# humanoid-17.net
KiCad netlist of a schematic drawn in EAGLE
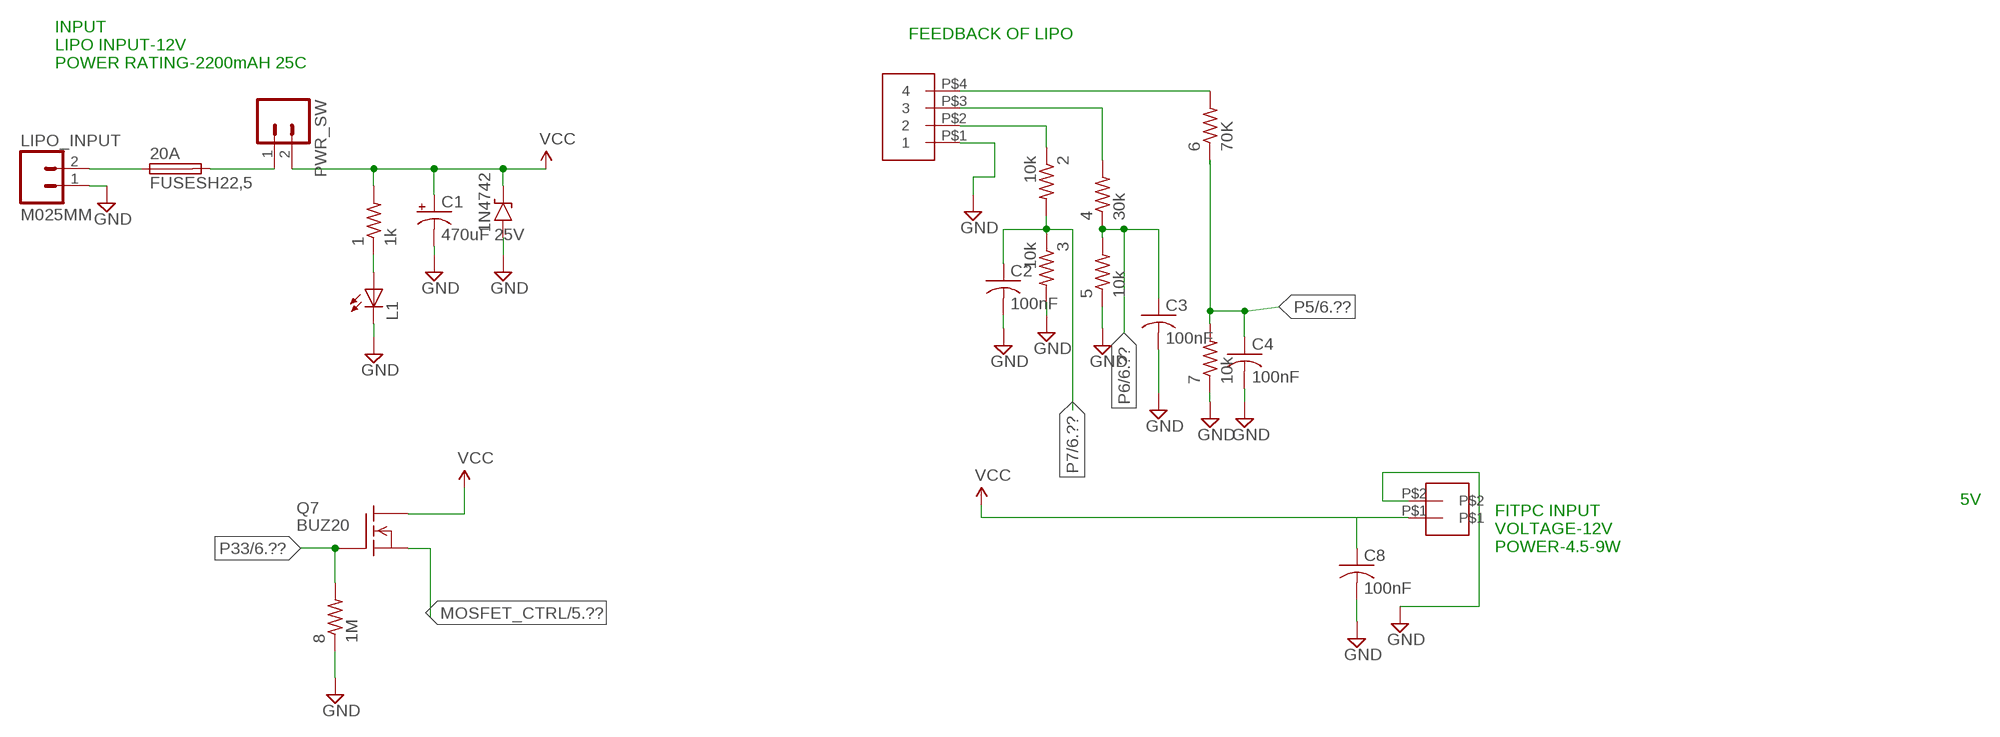
[diagram p0: schematic, sheet 1]
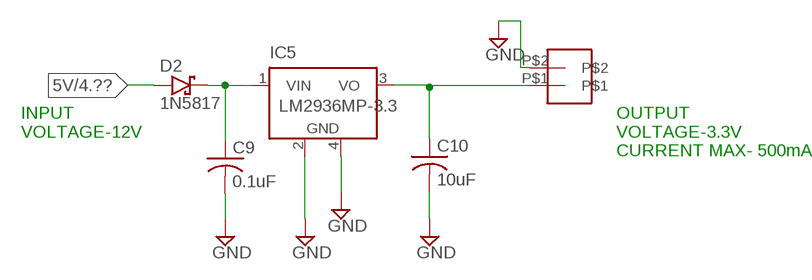
[diagram p1: schematic, sheet 2]
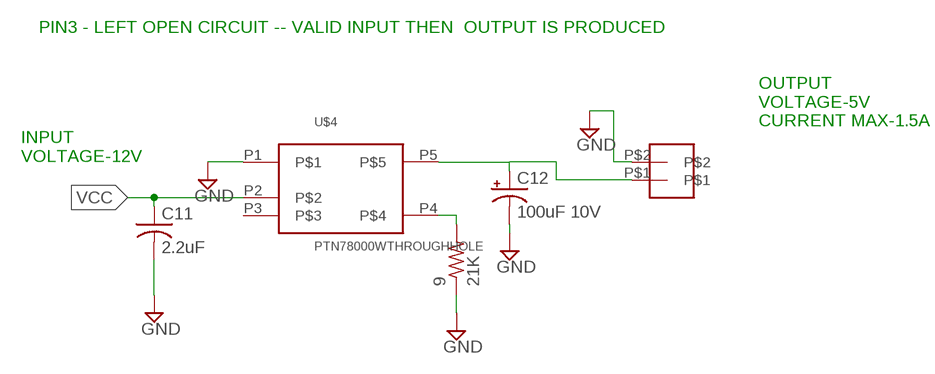
[diagram p2: schematic, sheet 3]
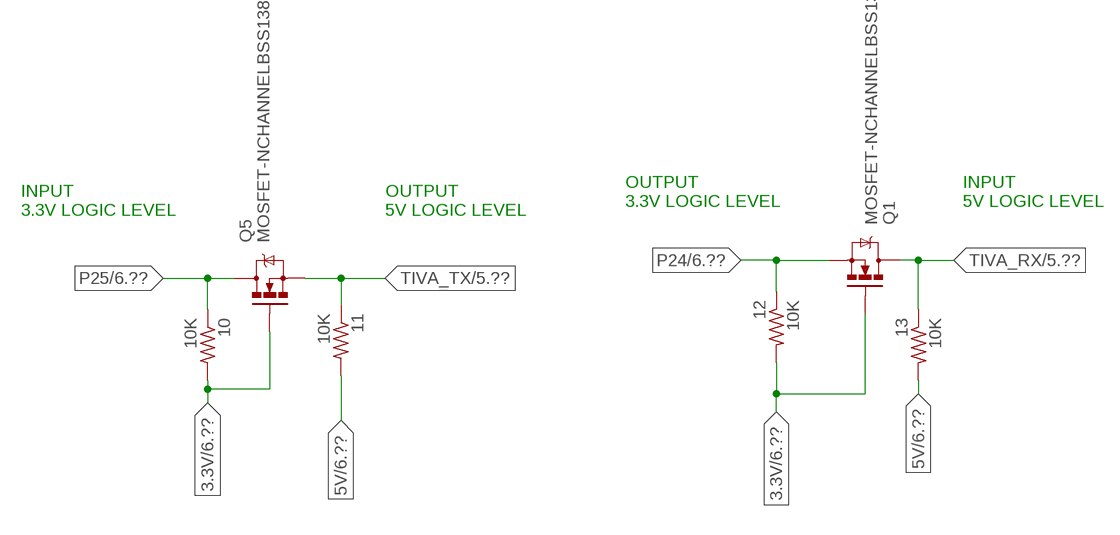
[diagram p3: schematic, sheet 4]
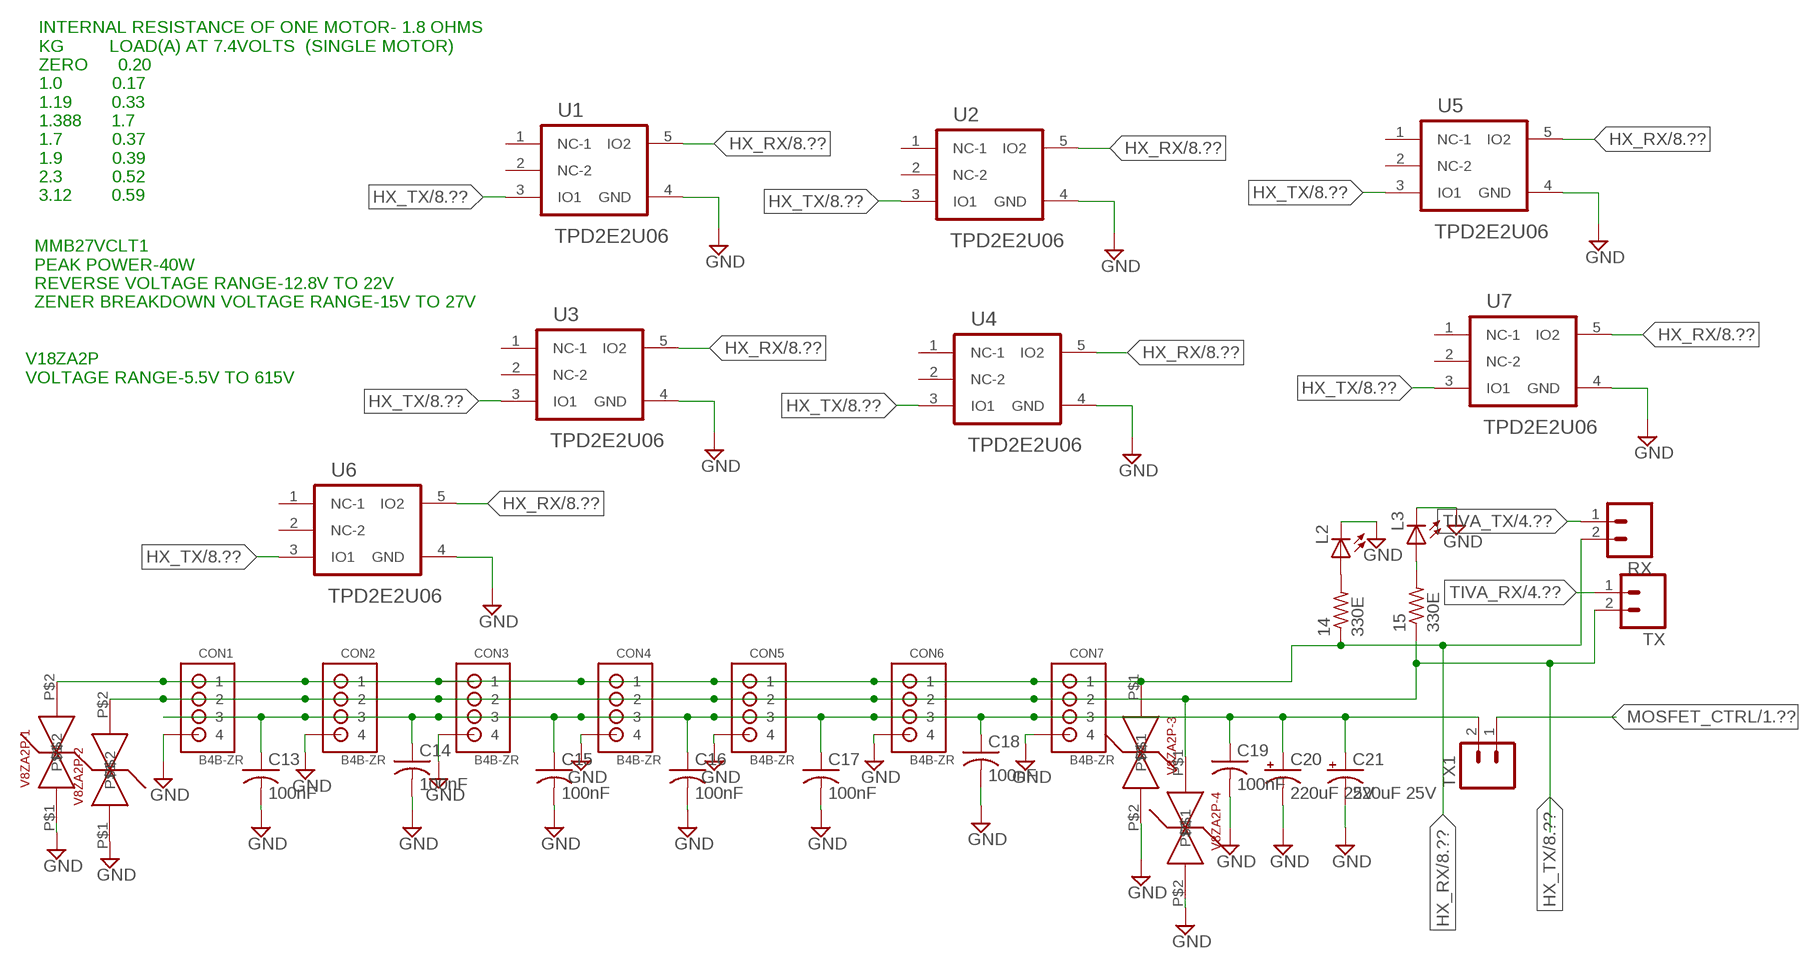
[diagram p4: schematic, sheet 5]
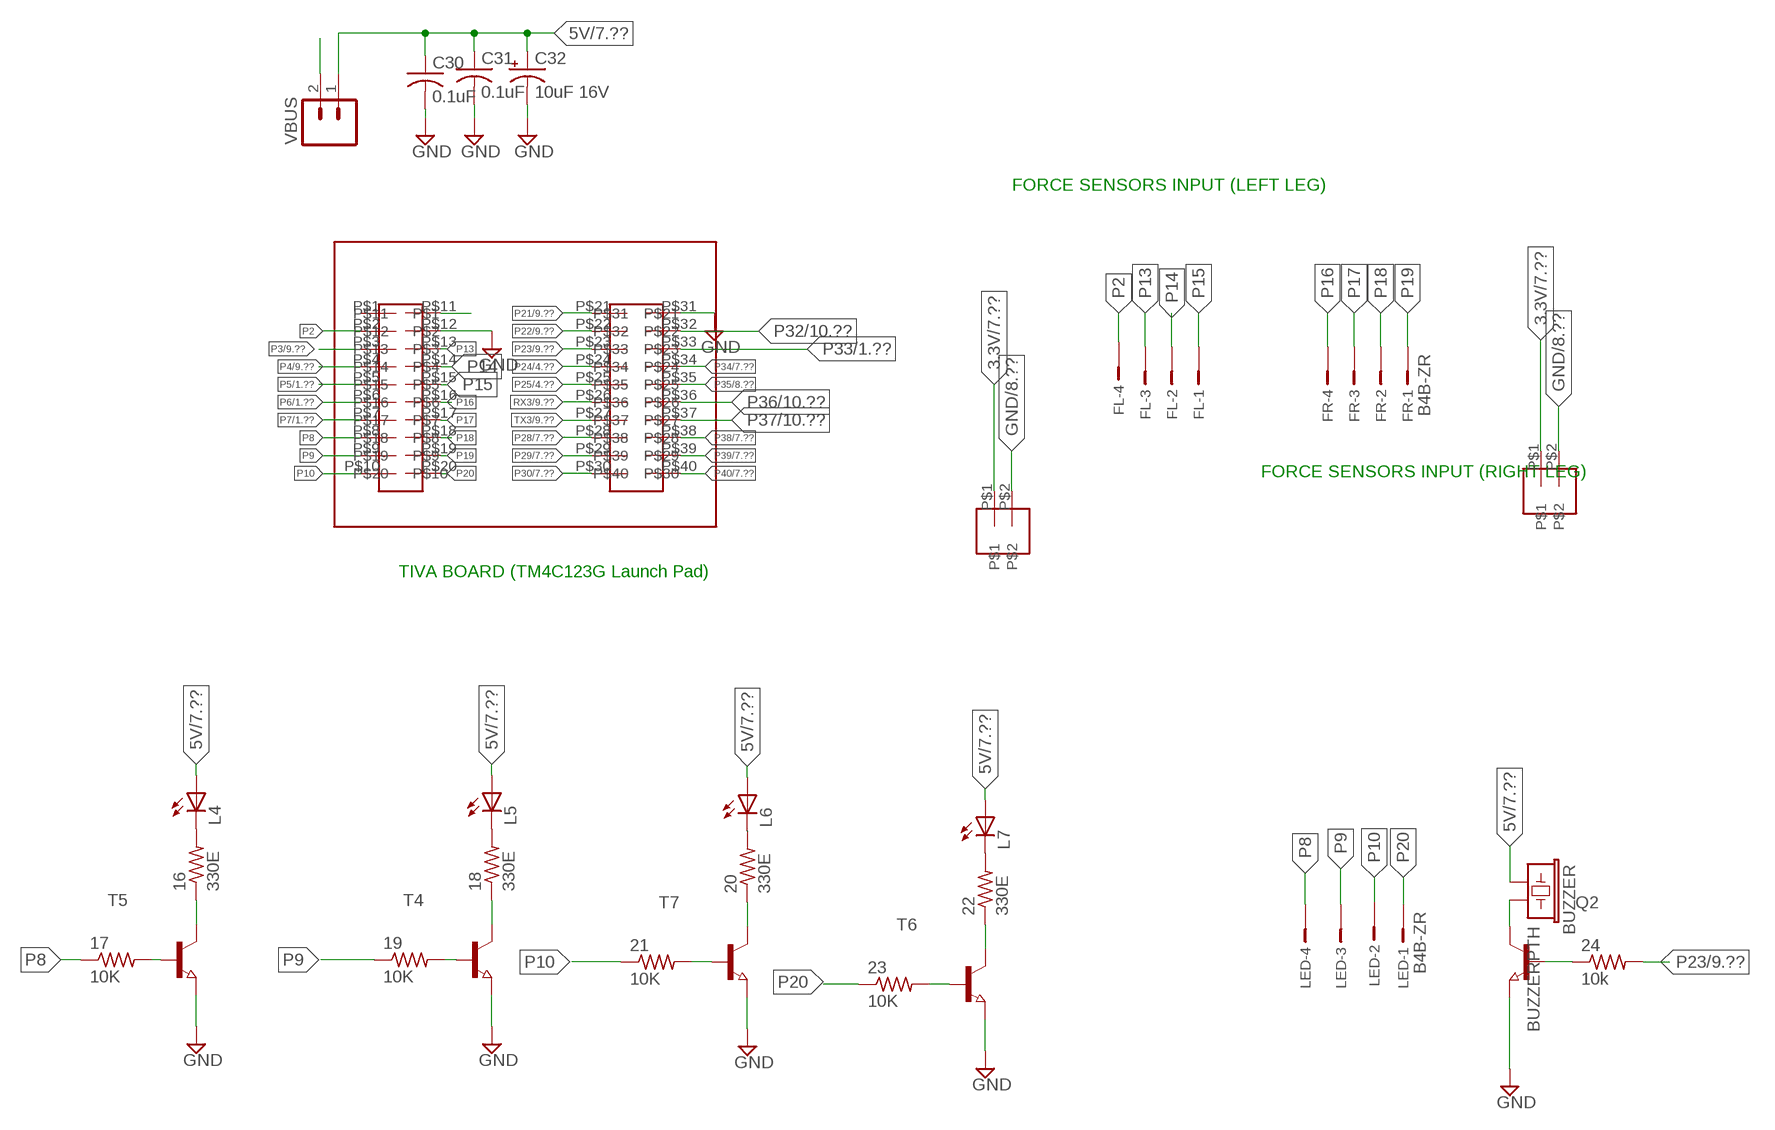
[diagram p5: schematic, sheet 6]
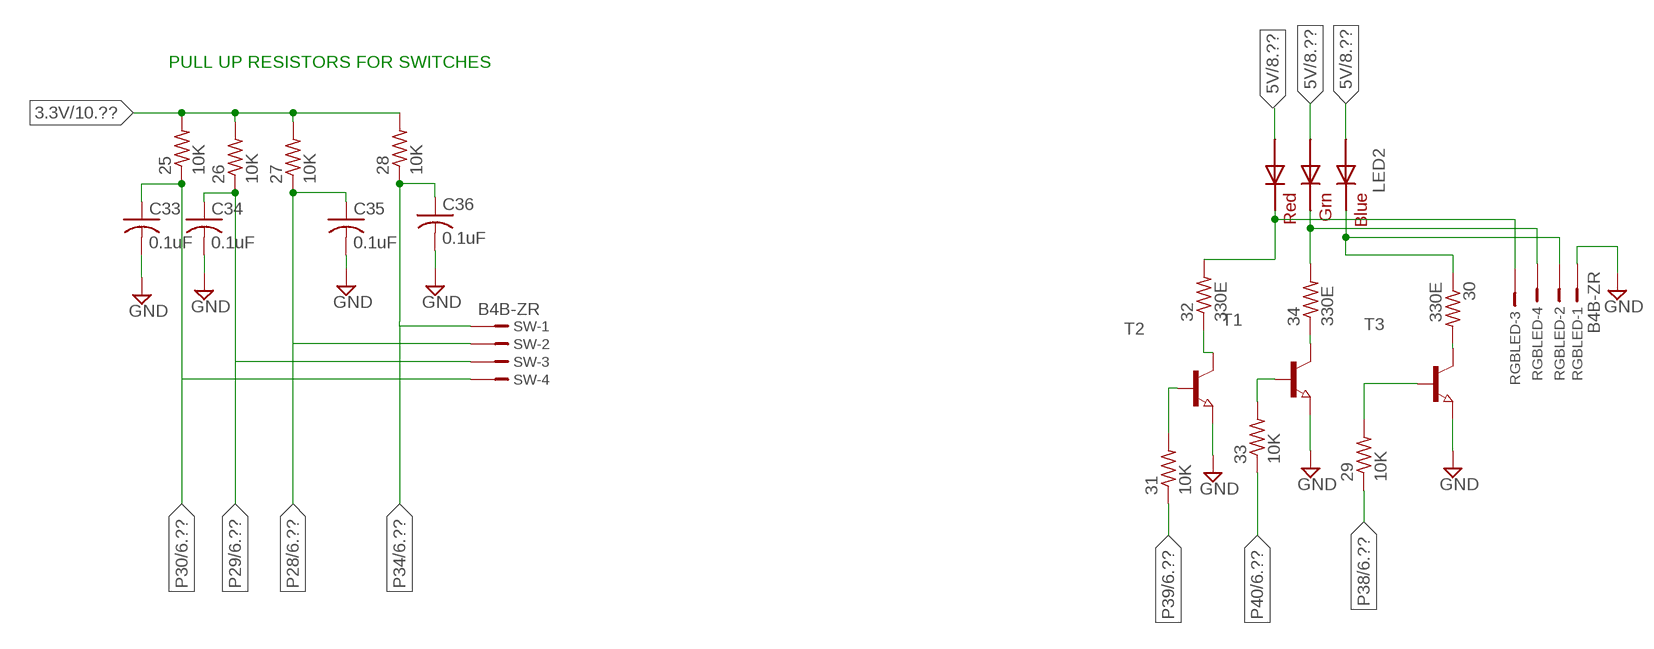
[diagram p6: schematic, sheet 7]
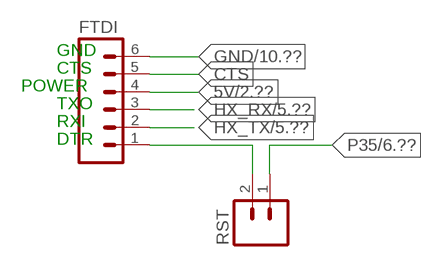
[diagram p7: schematic, sheet 8]
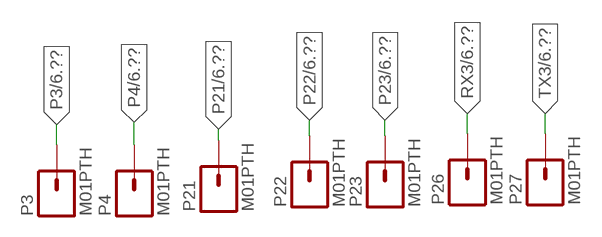
[diagram p8: schematic, sheet 9]
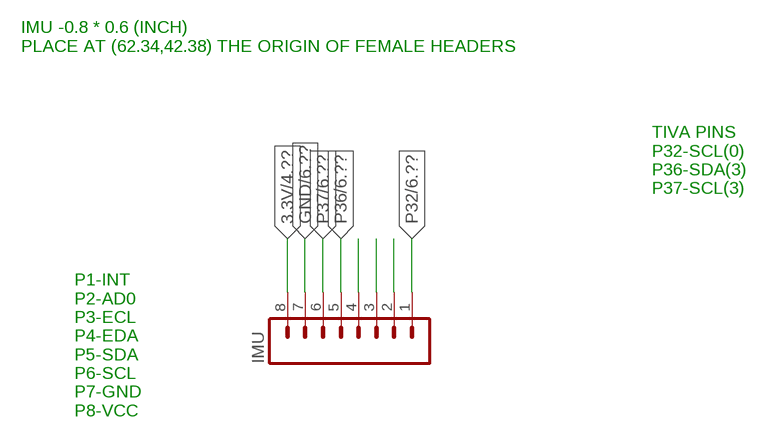
[diagram p9: schematic, sheet 10]

(export (version "E")
  (design (tool "Eeschema 10.0.6"))
  (components
    (comp (ref "5V1")
      (value "2PINRIGHT")
      (footprint "eagle-import:2PINRIGHT")
      (libsource (lib "eagle-import") (part "2PINRIGHT"))
    )
    (comp (ref "9")
      (value "21K")
      (footprint "eagle-import:R0805")
      (libsource (lib "eagle-import") (part "R-US_R0805"))
    )
    (comp (ref "C11")
      (value "2.2uF")
      (footprint "eagle-import:C1206")
      (fields
        (field (name "MANUFACTURER") "TDK")
        (field (name "MOUSER_PARTNO") "810-C1608X7R1A225K")
        (field (name "PARTNO") "C1608X7R1A225K080AC")
      )
      (libsource (lib "eagle-import") (part "resistor_C-USC1206"))
    )
    (comp (ref "C12")
      (value "100uF 10V")
      (footprint "eagle-import:PANASONIC_E")
      (fields
        (field (name "MANUFACTURER") "Panasonic")
        (field (name "MOUSER_PARTNO") " 667-EEE-HA1A101P")
        (field (name "PARTNO") "EEE-HA1A101P")
      )
      (libsource (lib "eagle-import") (part "CPOL-USE"))
    )
    (comp (ref "U$4")
      (value "PTN78000WTHROUGHHOLE")
      (footprint "eagle-import:PTN78000W")
      (libsource (lib "eagle-import") (part "PTN78000WTHROUGHHOLE"))
    )
    (comp (ref "3.3VL")
      (value "2PINRIGHT")
      (footprint "eagle-import:2PINRIGHT")
      (libsource (lib "eagle-import") (part "2PINRIGHT"))
    )
    (comp (ref "3.3VR")
      (value "2PINRIGHT")
      (footprint "eagle-import:2PINRIGHT")
      (libsource (lib "eagle-import") (part "2PINRIGHT"))
    )
    (comp (ref "16")
      (value "330E")
      (footprint "eagle-import:R0805")
      (libsource (lib "eagle-import") (part "R-US_R0805"))
    )
    (comp (ref "17")
      (value "10K")
      (footprint "eagle-import:R0805")
      (libsource (lib "eagle-import") (part "R-US_R0805"))
    )
    (comp (ref "18")
      (value "330E")
      (footprint "eagle-import:R0805")
      (libsource (lib "eagle-import") (part "R-US_R0805"))
    )
    (comp (ref "19")
      (value "10K")
      (footprint "eagle-import:R0805")
      (libsource (lib "eagle-import") (part "R-US_R0805"))
    )
    (comp (ref "20")
      (value "330E")
      (footprint "eagle-import:R0805")
      (libsource (lib "eagle-import") (part "R-US_R0805"))
    )
    (comp (ref "21")
      (value "10K")
      (footprint "eagle-import:R0805")
      (libsource (lib "eagle-import") (part "R-US_R0805"))
    )
    (comp (ref "22")
      (value "330E")
      (footprint "eagle-import:R0805")
      (libsource (lib "eagle-import") (part "R-US_R0805"))
    )
    (comp (ref "23")
      (value "10K")
      (footprint "eagle-import:R0805")
      (libsource (lib "eagle-import") (part "R-US_R0805"))
    )
    (comp (ref "24")
      (value "10k")
      (footprint "eagle-import:R0805")
      (libsource (lib "eagle-import") (part "R-US_R0805"))
    )
    (comp (ref "BUZZER")
      (value "BUZZERPTH")
      (footprint "eagle-import:BUZZER-12MM")
      (libsource (lib "eagle-import") (part "BUZZERPTH"))
    )
    (comp (ref "C30")
      (value "0.1uF")
      (footprint "eagle-import:C1206")
      (libsource (lib "eagle-import") (part "resistor_C-USC1206"))
    )
    (comp (ref "C31")
      (value "0.1uF")
      (footprint "eagle-import:C1206")
      (libsource (lib "eagle-import") (part "resistor_C-USC1206"))
    )
    (comp (ref "C32")
      (value "10uF 16V")
      (footprint "eagle-import:PANASONIC_B")
      (libsource (lib "eagle-import") (part "CPOL-USB"))
    )
    (comp (ref "FL")
      (value "B4B-ZR")
      (footprint "eagle-import:B4B-ZR")
      (fields
        (field (name "MF") "FARNELL")
        (field (name "MPN") "B4B-ZR(LF)(SN)")
        (field (name "OC_NEWARK") "unknown")
      )
      (libsource (lib "eagle-import") (part "?4B-ZRB"))
    )
    (comp (ref "FR")
      (value "B4B-ZR")
      (footprint "eagle-import:B4B-ZR")
      (fields
        (field (name "MF") "FARNELL")
        (field (name "MPN") "B4B-ZR(LF)(SN)")
        (field (name "OC_NEWARK") "unknown")
      )
      (libsource (lib "eagle-import") (part "?4B-ZRB"))
    )
    (comp (ref "L4")
      (value "LEDCHIPLED_1206")
      (footprint "eagle-import:CHIPLED_1206")
      (libsource (lib "eagle-import") (part "LEDCHIPLED_1206"))
    )
    (comp (ref "L5")
      (value "LEDCHIPLED_1206")
      (footprint "eagle-import:CHIPLED_1206")
      (libsource (lib "eagle-import") (part "LEDCHIPLED_1206"))
    )
    (comp (ref "L6")
      (value "LEDCHIPLED_1206")
      (footprint "eagle-import:CHIPLED_1206")
      (libsource (lib "eagle-import") (part "LEDCHIPLED_1206"))
    )
    (comp (ref "L7")
      (value "LEDCHIPLED_1206")
      (footprint "eagle-import:CHIPLED_1206")
      (libsource (lib "eagle-import") (part "LEDCHIPLED_1206"))
    )
    (comp (ref "LED")
      (value "B4B-ZR")
      (footprint "eagle-import:B4B-ZR")
      (fields
        (field (name "MF") "FARNELL")
        (field (name "MPN") "B4B-ZR(LF)(SN)")
        (field (name "OC_NEWARK") "unknown")
      )
      (libsource (lib "eagle-import") (part "?4B-ZRB"))
    )
    (comp (ref "Q2")
      (value "NPN-TRANSISTOR_SOT23")
      (footprint "eagle-import:SOT23")
      (libsource (lib "eagle-import") (part "NPN-TRANSISTOR_SOT23"))
    )
    (comp (ref "T4")
      (value "NPN-TRANSISTOR_SOT23")
      (footprint "eagle-import:SOT23")
      (libsource (lib "eagle-import") (part "NPN-TRANSISTOR_SOT23"))
    )
    (comp (ref "T5")
      (value "NPN-TRANSISTOR_SOT23")
      (footprint "eagle-import:SOT23")
      (libsource (lib "eagle-import") (part "NPN-TRANSISTOR_SOT23"))
    )
    (comp (ref "T6")
      (value "NPN-TRANSISTOR_SOT23")
      (footprint "eagle-import:SOT23")
      (libsource (lib "eagle-import") (part "NPN-TRANSISTOR_SOT23"))
    )
    (comp (ref "T7")
      (value "NPN-TRANSISTOR_SOT23")
      (footprint "eagle-import:SOT23")
      (libsource (lib "eagle-import") (part "NPN-TRANSISTOR_SOT23"))
    )
    (comp (ref "U$1")
      (value "TIVA")
      (footprint "eagle-import:TIVA")
      (libsource (lib "eagle-import") (part "TIVA"))
    )
    (comp (ref "VBUS")
      (value "M02PTH")
      (footprint "eagle-import:1X02")
      (libsource (lib "eagle-import") (part "M02PTH"))
    )
    (comp (ref "14")
      (value "330E")
      (footprint "eagle-import:R0805")
      (libsource (lib "eagle-import") (part "R-US_R0805"))
    )
    (comp (ref "15")
      (value "330E")
      (footprint "eagle-import:R0805")
      (libsource (lib "eagle-import") (part "R-US_R0805"))
    )
    (comp (ref "C13")
      (value "100nF")
      (footprint "eagle-import:C1206")
      (fields (field (name "MANUFACTURER") "KEMET") (field (name "PARTNO") "C1206C104K5RACTU"))
      (libsource (lib "eagle-import") (part "C-USC1206"))
    )
    (comp (ref "C14")
      (value "100nF")
      (footprint "eagle-import:C1206")
      (fields (field (name "MANUFACTURER") "KEMET") (field (name "PARTNO") "C1206C104K5RACTU"))
      (libsource (lib "eagle-import") (part "C-USC1206"))
    )
    (comp (ref "C15")
      (value "100nF")
      (footprint "eagle-import:C1206")
      (fields (field (name "MANUFACTURER") "KEMET") (field (name "PARTNO") "C1206C104K5RACTU"))
      (libsource (lib "eagle-import") (part "C-USC1206"))
    )
    (comp (ref "C16")
      (value "100nF")
      (footprint "eagle-import:C1206")
      (fields (field (name "MANUFACTURER") "KEMET") (field (name "PARTNO") "C1206C104K5RACTU"))
      (libsource (lib "eagle-import") (part "C-USC1206"))
    )
    (comp (ref "C17")
      (value "100nF")
      (footprint "eagle-import:C1206")
      (fields (field (name "MANUFACTURER") "KEMET") (field (name "PARTNO") "C1206C104K5RACTU"))
      (libsource (lib "eagle-import") (part "C-USC1206"))
    )
    (comp (ref "C18")
      (value "100nF")
      (footprint "eagle-import:C1206")
      (fields (field (name "MANUFACTURER") "KEMET") (field (name "PARTNO") "C1206C104K5RACTU"))
      (libsource (lib "eagle-import") (part "C-USC1206"))
    )
    (comp (ref "C19")
      (value "100nF")
      (footprint "eagle-import:C1206")
      (fields (field (name "MANUFACTURER") "KEMET") (field (name "PARTNO") "C1206C104K5RACTU"))
      (libsource (lib "eagle-import") (part "C-USC1206"))
    )
    (comp (ref "C20")
      (value "220uF 25V")
      (footprint "eagle-import:PANASONIC_G")
      (fields
        (field (name "MANUFACTURER") " PANASONIC ELECTRONIC COMPONENTS")
        (field (name "MOUSER_PARTNO") "667-EEE-1EA221P")
        (field (name "PARTNO") "EEE-1EA221P")
      )
      (libsource (lib "eagle-import") (part "CPOL-USG"))
    )
    (comp (ref "C21")
      (value "220uF 25V")
      (footprint "eagle-import:PANASONIC_G")
      (fields
        (field (name "MANUFACTURER") " PANASONIC ELECTRONIC COMPONENTS")
        (field (name "MOUSER_PARTNO") "667-EEE-1EA221P")
        (field (name "PARTNO") "EEE-1EA221P")
      )
      (libsource (lib "eagle-import") (part "CPOL-USG"))
    )
    (comp (ref "CON1")
      (value "B4B-ZR")
      (footprint "eagle-import:B4B-ZR")
      (fields (field (name "MF") "FARNELL") (field (name "MPN") "B4B-ZR(LF)(SN)"))
      (libsource (lib "eagle-import") (part "B4B-ZR"))
    )
    (comp (ref "CON2")
      (value "B4B-ZR")
      (footprint "eagle-import:B4B-ZR")
      (fields (field (name "MF") "FARNELL") (field (name "MPN") "B4B-ZR(LF)(SN)"))
      (libsource (lib "eagle-import") (part "B4B-ZR"))
    )
    (comp (ref "CON3")
      (value "B4B-ZR")
      (footprint "eagle-import:B4B-ZR")
      (fields (field (name "MF") "FARNELL") (field (name "MPN") "B4B-ZR(LF)(SN)"))
      (libsource (lib "eagle-import") (part "B4B-ZR"))
    )
    (comp (ref "CON4")
      (value "B4B-ZR")
      (footprint "eagle-import:B4B-ZR")
      (fields (field (name "MF") "FARNELL") (field (name "MPN") "B4B-ZR(LF)(SN)"))
      (libsource (lib "eagle-import") (part "B4B-ZR"))
    )
    (comp (ref "CON5")
      (value "B4B-ZR")
      (footprint "eagle-import:B4B-ZR")
      (fields (field (name "MF") "FARNELL") (field (name "MPN") "B4B-ZR(LF)(SN)"))
      (libsource (lib "eagle-import") (part "B4B-ZR"))
    )
    (comp (ref "CON6")
      (value "B4B-ZR")
      (footprint "eagle-import:B4B-ZR")
      (fields (field (name "MF") "FARNELL") (field (name "MPN") "B4B-ZR(LF)(SN)"))
      (libsource (lib "eagle-import") (part "B4B-ZR"))
    )
    (comp (ref "CON7")
      (value "B4B-ZR")
      (footprint "eagle-import:B4B-ZR")
      (fields (field (name "MF") "FARNELL") (field (name "MPN") "B4B-ZR(LF)(SN)"))
      (libsource (lib "eagle-import") (part "B4B-ZR"))
    )
    (comp (ref "L2")
      (value "LEDCHIPLED_1206")
      (footprint "eagle-import:CHIPLED_1206")
      (libsource (lib "eagle-import") (part "LEDCHIPLED_1206"))
    )
    (comp (ref "L3")
      (value "LEDCHIPLED_1206")
      (footprint "eagle-import:CHIPLED_1206")
      (libsource (lib "eagle-import") (part "LEDCHIPLED_1206"))
    )
    (comp (ref "RX")
      (value "M02PTH")
      (footprint "eagle-import:1X02")
      (libsource (lib "eagle-import") (part "M02PTH"))
    )
    (comp (ref "TX")
      (value "M02PTH")
      (footprint "eagle-import:1X02")
      (libsource (lib "eagle-import") (part "M02PTH"))
    )
    (comp (ref "TX1")
      (value "M02PTH")
      (footprint "eagle-import:1X02")
      (libsource (lib "eagle-import") (part "M02PTH"))
    )
    (comp (ref "U1")
      (value "TPD2E2U06")
      (footprint "eagle-import:SOT50P160X60-5N")
      (fields (field (name "MPN") "TPD2E001IDRLRQ1"))
      (libsource (lib "eagle-import") (part "TPD2E2U06"))
    )
    (comp (ref "U2")
      (value "TPD2E2U06")
      (footprint "eagle-import:SOT50P160X60-5N")
      (fields (field (name "MPN") "TPD2E001IDRLRQ1"))
      (libsource (lib "eagle-import") (part "TPD2E2U06"))
    )
    (comp (ref "U3")
      (value "TPD2E2U06")
      (footprint "eagle-import:SOT50P160X60-5N")
      (fields (field (name "MPN") "TPD2E001IDRLRQ1"))
      (libsource (lib "eagle-import") (part "TPD2E2U06"))
    )
    (comp (ref "U4")
      (value "TPD2E2U06")
      (footprint "eagle-import:SOT50P160X60-5N")
      (fields (field (name "MPN") "TPD2E001IDRLRQ1"))
      (libsource (lib "eagle-import") (part "TPD2E2U06"))
    )
    (comp (ref "U5")
      (value "TPD2E2U06")
      (footprint "eagle-import:SOT50P160X60-5N")
      (fields (field (name "MPN") "TPD2E001IDRLRQ1"))
      (libsource (lib "eagle-import") (part "TPD2E2U06"))
    )
    (comp (ref "U6")
      (value "TPD2E2U06")
      (footprint "eagle-import:SOT50P160X60-5N")
      (fields (field (name "MPN") "TPD2E001IDRLRQ1"))
      (libsource (lib "eagle-import") (part "TPD2E2U06"))
    )
    (comp (ref "U7")
      (value "TPD2E2U06")
      (footprint "eagle-import:SOT50P160X60-5N")
      (fields (field (name "MPN") "TPD2E001IDRLRQ1"))
      (libsource (lib "eagle-import") (part "TPD2E2U06"))
    )
    (comp (ref "V8ZA2P-1")
      (value "V18ZA2P")
      (footprint "eagle-import:V18ZA2P")
      (libsource (lib "eagle-import") (part "V18ZA2P"))
    )
    (comp (ref "V8ZA2P-2")
      (value "V18ZA2P")
      (footprint "eagle-import:V18ZA2P")
      (libsource (lib "eagle-import") (part "V18ZA2P"))
    )
    (comp (ref "V8ZA2P-3")
      (value "V18ZA2P")
      (footprint "eagle-import:V18ZA2P")
      (libsource (lib "eagle-import") (part "V18ZA2P"))
    )
    (comp (ref "V8ZA2P-4")
      (value "V18ZA2P")
      (footprint "eagle-import:V18ZA2P")
      (libsource (lib "eagle-import") (part "V18ZA2P"))
    )
    (comp (ref "10")
      (value "10K")
      (footprint "eagle-import:R0805")
      (libsource (lib "eagle-import") (part "R-US_R0805"))
    )
    (comp (ref "11")
      (value "10K")
      (footprint "eagle-import:R0805")
      (libsource (lib "eagle-import") (part "R-US_R0805"))
    )
    (comp (ref "12")
      (value "10K")
      (footprint "eagle-import:R0805")
      (libsource (lib "eagle-import") (part "R-US_R0805"))
    )
    (comp (ref "13")
      (value "10K")
      (footprint "eagle-import:R0805")
      (libsource (lib "eagle-import") (part "R-US_R0805"))
    )
    (comp (ref "Q1")
      (value "MOSFET-NCHANNELBSS138")
      (footprint "eagle-import:SOT23")
      (libsource (lib "eagle-import") (part "MOSFET-NCHANNELBSS138"))
    )
    (comp (ref "Q5")
      (value "MOSFET-NCHANNELBSS138")
      (footprint "eagle-import:SOT23")
      (libsource (lib "eagle-import") (part "MOSFET-NCHANNELBSS138"))
    )
    (comp (ref "IMU")
      (value "M081X08")
      (footprint "eagle-import:1X08")
      (libsource (lib "eagle-import") (part "M081X08"))
    )
    (comp (ref "3.3V1")
      (value "2PINRIGHT")
      (footprint "eagle-import:2PINRIGHT")
      (libsource (lib "eagle-import") (part "2PINRIGHT"))
    )
    (comp (ref "C9")
      (value "0.1uF")
      (footprint "eagle-import:C1206")
      (fields (field (name "MANUFACTURER") "KEMET") (field (name "PARTNO") "C1206C104K5RACTU"))
      (libsource (lib "eagle-import") (part "C-USC1206"))
    )
    (comp (ref "C10")
      (value "10uF")
      (footprint "eagle-import:C1206")
      (fields (field (name "MANUFACTURER") "KEMET") (field (name "PARTNO") "C1206C104K5RACTU"))
      (libsource (lib "eagle-import") (part "C-USC1206"))
    )
    (comp (ref "D2")
      (value "1N5817")
      (footprint "eagle-import:DO41-3")
      (libsource (lib "eagle-import") (part "1N5817"))
    )
    (comp (ref "IC5")
      (value "LM2936MP-3.3")
      (footprint "eagle-import:SOT223")
      (fields
        (field (name "MF") "NATIONAL SEMICONDUCTOR")
        (field (name "MPN") "LM2936MP-3.3/NOPB")
        (field (name "OC_NEWARK") "unknown")
      )
      (libsource (lib "eagle-import") (part "LM2936MP?-3.3"))
    )
    (comp (ref "FTDI")
      (value "M06LOCK")
      (footprint "eagle-import:1X06_LOCK")
      (libsource (lib "eagle-import") (part "M06LOCK"))
    )
    (comp (ref "RST")
      (value "M02PTH")
      (footprint "eagle-import:1X02")
      (libsource (lib "eagle-import") (part "M02PTH"))
    )
    (comp (ref "P3")
      (value "M01PTH")
      (footprint "eagle-import:1X01")
      (libsource (lib "eagle-import") (part "M01PTH"))
    )
    (comp (ref "P4")
      (value "M01PTH")
      (footprint "eagle-import:1X01")
      (libsource (lib "eagle-import") (part "M01PTH"))
    )
    (comp (ref "P21")
      (value "M01PTH")
      (footprint "eagle-import:1X01")
      (libsource (lib "eagle-import") (part "M01PTH"))
    )
    (comp (ref "P22")
      (value "M01PTH")
      (footprint "eagle-import:1X01")
      (libsource (lib "eagle-import") (part "M01PTH"))
    )
    (comp (ref "P23")
      (value "M01PTH")
      (footprint "eagle-import:1X01")
      (libsource (lib "eagle-import") (part "M01PTH"))
    )
    (comp (ref "P26")
      (value "M01PTH")
      (footprint "eagle-import:1X01")
      (libsource (lib "eagle-import") (part "M01PTH"))
    )
    (comp (ref "P27")
      (value "M01PTH")
      (footprint "eagle-import:1X01")
      (libsource (lib "eagle-import") (part "M01PTH"))
    )
    (comp (ref "1")
      (value "1k")
      (footprint "eagle-import:R0805")
      (libsource (lib "eagle-import") (part "R-US_R0805"))
    )
    (comp (ref "1N4742")
      (value "1N47XX3")
      (footprint "eagle-import:DO41-3")
      (libsource (lib "eagle-import") (part "1N47XX3"))
    )
    (comp (ref "2")
      (value "10k")
      (footprint "eagle-import:R0805")
      (libsource (lib "eagle-import") (part "R-US_R0805"))
    )
    (comp (ref "3")
      (value "10k")
      (footprint "eagle-import:R0805")
      (libsource (lib "eagle-import") (part "R-US_R0805"))
    )
    (comp (ref "4")
      (value "30k")
      (footprint "eagle-import:R0805")
      (libsource (lib "eagle-import") (part "R-US_R0805"))
    )
    (comp (ref "5")
      (value "10k")
      (footprint "eagle-import:R0805")
      (libsource (lib "eagle-import") (part "R-US_R0805"))
    )
    (comp (ref "6")
      (value "70K")
      (footprint "eagle-import:R0805")
      (libsource (lib "eagle-import") (part "R-US_R0805"))
    )
    (comp (ref "7")
      (value "10k")
      (footprint "eagle-import:R0805")
      (libsource (lib "eagle-import") (part "R-US_R0805"))
    )
    (comp (ref "8")
      (value "1M")
      (footprint "eagle-import:R0805")
      (libsource (lib "eagle-import") (part "R-US_R0805"))
    )
    (comp (ref "20A")
      (value "FUSESH22,5")
      (footprint "eagle-import:SH22,5")
      (libsource (lib "eagle-import") (part "FUSESH22,5"))
    )
    (comp (ref "C1")
      (value "470uF 25V")
      (footprint "eagle-import:PANASONIC_G")
      (fields
        (field (name "MANUFACTURER") " PANASONIC ELECTRONIC COMPONENTS")
        (field (name "PARTNO") "EEEFK1E471AP")
      )
      (libsource (lib "eagle-import") (part "CPOL-USG"))
    )
    (comp (ref "C2")
      (value "100nF")
      (footprint "eagle-import:C1206")
      (fields (field (name "MANUFACTURER") "KEMET") (field (name "PARTNO") "C1206C104K5RACTU"))
      (libsource (lib "eagle-import") (part "C-USC1206"))
    )
    (comp (ref "C3")
      (value "100nF")
      (footprint "eagle-import:C1206")
      (fields (field (name "MANUFACTURER") "KEMET") (field (name "PARTNO") "C1206C104K5RACTU"))
      (libsource (lib "eagle-import") (part "C-USC1206"))
    )
    (comp (ref "C4")
      (value "100nF")
      (footprint "eagle-import:C1206")
      (fields (field (name "MANUFACTURER") "KEMET") (field (name "PARTNO") "C1206C104K5RACTU"))
      (libsource (lib "eagle-import") (part "C-USC1206"))
    )
    (comp (ref "C8")
      (value "100nF")
      (footprint "eagle-import:C1206")
      (fields (field (name "MANUFACTURER") "KEMET") (field (name "PARTNO") "C1206C104K5RACTU"))
      (libsource (lib "eagle-import") (part "C-USC1206"))
    )
    (comp (ref "FITPC")
      (value "2PINRIGHT")
      (footprint "eagle-import:2PINRIGHT")
      (libsource (lib "eagle-import") (part "2PINRIGHT"))
    )
    (comp (ref "L1")
      (value "LEDCHIPLED_1206")
      (footprint "eagle-import:CHIPLED_1206")
      (libsource (lib "eagle-import") (part "LEDCHIPLED_1206"))
    )
    (comp (ref "LIPO_INPUT")
      (value "M025MM")
      (footprint "eagle-import:SCREWTERMINAL-5MM-2")
      (libsource (lib "eagle-import") (part "SparkFun-Connectors_M025MM"))
    )
    (comp (ref "PWR_SW")
      (value "M02PTH")
      (footprint "eagle-import:1X02")
      (libsource (lib "eagle-import") (part "M02PTH"))
    )
    (comp (ref "Q7")
      (value "BUZ20")
      (footprint "eagle-import:TO220")
      (libsource (lib "eagle-import") (part "BUZ20"))
    )
    (comp (ref "U$2")
      (value "4PINRIGHT")
      (footprint "eagle-import:4PINRIGHT")
      (libsource (lib "eagle-import") (part "4PINRIGHT"))
    )
    (comp (ref "25")
      (value "10K")
      (footprint "eagle-import:R0805")
      (libsource (lib "eagle-import") (part "R-US_R0805"))
    )
    (comp (ref "26")
      (value "10K")
      (footprint "eagle-import:R0805")
      (libsource (lib "eagle-import") (part "R-US_R0805"))
    )
    (comp (ref "27")
      (value "10K")
      (footprint "eagle-import:R0805")
      (libsource (lib "eagle-import") (part "R-US_R0805"))
    )
    (comp (ref "28")
      (value "10K")
      (footprint "eagle-import:R0805")
      (libsource (lib "eagle-import") (part "R-US_R0805"))
    )
    (comp (ref "29")
      (value "10K")
      (footprint "eagle-import:R0805")
      (libsource (lib "eagle-import") (part "R-US_R0805"))
    )
    (comp (ref "30")
      (value "330E")
      (footprint "eagle-import:R0805")
      (libsource (lib "eagle-import") (part "R-US_R0805"))
    )
    (comp (ref "31")
      (value "10K")
      (footprint "eagle-import:R0805")
      (libsource (lib "eagle-import") (part "R-US_R0805"))
    )
    (comp (ref "32")
      (value "330E")
      (footprint "eagle-import:R0805")
      (libsource (lib "eagle-import") (part "R-US_R0805"))
    )
    (comp (ref "33")
      (value "10K")
      (footprint "eagle-import:R0805")
      (libsource (lib "eagle-import") (part "R-US_R0805"))
    )
    (comp (ref "34")
      (value "330E")
      (footprint "eagle-import:R0805")
      (libsource (lib "eagle-import") (part "R-US_R0805"))
    )
    (comp (ref "C33")
      (value "0.1uF")
      (footprint "eagle-import:C1206")
      (fields
        (field (name "MANUFACTURER") "Kemet")
        (field (name "MOUSER_PARTNO") "80-C0805C104M5R")
        (field (name "PARTNO") "C0805C104M5RACTU")
      )
      (libsource (lib "eagle-import") (part "C-USC1206"))
    )
    (comp (ref "C34")
      (value "0.1uF")
      (footprint "eagle-import:C1206")
      (fields
        (field (name "MANUFACTURER") "Kemet")
        (field (name "MOUSER_PARTNO") "80-C0805C104M5R")
        (field (name "PARTNO") "C0805C104M5RACTU")
      )
      (libsource (lib "eagle-import") (part "C-USC1206"))
    )
    (comp (ref "C35")
      (value "0.1uF")
      (footprint "eagle-import:C1206")
      (fields
        (field (name "MANUFACTURER") "Kemet")
        (field (name "MOUSER_PARTNO") "80-C0805C104M5R")
        (field (name "PARTNO") "C0805C104M5RACTU")
      )
      (libsource (lib "eagle-import") (part "C-USC1206"))
    )
    (comp (ref "C36")
      (value "0.1uF")
      (footprint "eagle-import:C1206")
      (fields
        (field (name "MANUFACTURER") "Kemet")
        (field (name "MOUSER_PARTNO") "80-C0805C104M5R")
        (field (name "PARTNO") "C0805C104M5RACTU")
      )
      (libsource (lib "eagle-import") (part "C-USC1206"))
    )
    (comp (ref "LED2")
      (value "RGBLED5050")
      (footprint "eagle-import:RGBLED5050")
      (libsource (lib "eagle-import") (part "RGBLED5050"))
    )
    (comp (ref "RGBLED")
      (value "B4B-ZR")
      (footprint "eagle-import:B4B-ZR")
      (fields
        (field (name "MF") "FARNELL")
        (field (name "MPN") "B4B-ZR(LF)(SN)")
        (field (name "OC_NEWARK") "unknown")
      )
      (libsource (lib "eagle-import") (part "?4B-ZRB"))
    )
    (comp (ref "SW")
      (value "B4B-ZR")
      (footprint "eagle-import:B4B-ZR")
      (fields
        (field (name "MF") "FARNELL")
        (field (name "MPN") "B4B-ZR(LF)(SN)")
        (field (name "OC_NEWARK") "unknown")
      )
      (libsource (lib "eagle-import") (part "?4B-ZRB"))
    )
    (comp (ref "T1")
      (value "NPN-TRANSISTOR_SOT23")
      (footprint "eagle-import:SOT23")
      (libsource (lib "eagle-import") (part "NPN-TRANSISTOR_SOT23"))
    )
    (comp (ref "T2")
      (value "NPN-TRANSISTOR_SOT23")
      (footprint "eagle-import:SOT23")
      (libsource (lib "eagle-import") (part "NPN-TRANSISTOR_SOT23"))
    )
    (comp (ref "T3")
      (value "NPN-TRANSISTOR_SOT23")
      (footprint "eagle-import:SOT23")
      (libsource (lib "eagle-import") (part "NPN-TRANSISTOR_SOT23"))
    )
  )
  (nets
    (net (code "1") (name "3.3V") (class "Default")
      (node (ref "10") (pin "2") (pinfunction "2_2") (pintype "passive"))
      (node (ref "12") (pin "2") (pinfunction "2_2") (pintype "passive"))
      (node (ref "25") (pin "2") (pinfunction "2_2") (pintype "passive"))
      (node (ref "26") (pin "2") (pinfunction "2_2") (pintype "passive"))
      (node (ref "27") (pin "2") (pinfunction "2_2") (pintype "passive"))
      (node (ref "28") (pin "2") (pinfunction "2_2") (pintype "passive"))
      (node (ref "3.3V1") (pin "P$1") (pinfunction "P$1_P$1") (pintype "bidirectional"))
      (node (ref "3.3VL") (pin "P$1") (pinfunction "P$1_P$1") (pintype "bidirectional"))
      (node (ref "3.3VR") (pin "P$1") (pinfunction "P$1_P$1") (pintype "bidirectional"))
      (node (ref "C10") (pin "1") (pinfunction "1_1") (pintype "passive"))
      (node (ref "IC5") (pin "3") (pinfunction "VO_3") (pintype "passive"))
      (node (ref "IMU") (pin "8") (pinfunction "8_8") (pintype "passive"))
      (node (ref "Q1") (pin "1") (pinfunction "G_1") (pintype "passive"))
      (node (ref "Q5") (pin "1") (pinfunction "G_1") (pintype "passive"))
    )
    (net (code "2") (name "5V") (class "Default")
      (node (ref "11") (pin "2") (pinfunction "2_2") (pintype "passive"))
      (node (ref "13") (pin "2") (pinfunction "2_2") (pintype "passive"))
      (node (ref "5V1") (pin "P$1") (pinfunction "P$1_P$1") (pintype "bidirectional"))
      (node (ref "BUZZER") (pin "+") (pinfunction "1_+") (pintype "passive"))
      (node (ref "C12") (pin "+") (pinfunction "+_+") (pintype "passive"))
      (node (ref "C30") (pin "1") (pinfunction "1_1") (pintype "passive"))
      (node (ref "C31") (pin "1") (pinfunction "1_1") (pintype "passive"))
      (node (ref "C32") (pin "+") (pinfunction "+_+") (pintype "passive"))
      (node (ref "D2") (pin "A") (pinfunction "A_A") (pintype "passive"))
      (node (ref "FTDI") (pin "4") (pinfunction "4_4") (pintype "passive"))
      (node (ref "L4") (pin "A") (pinfunction "A_A") (pintype "passive"))
      (node (ref "L5") (pin "A") (pinfunction "A_A") (pintype "passive"))
      (node (ref "L6") (pin "A") (pinfunction "A_A") (pintype "passive"))
      (node (ref "L7") (pin "A") (pinfunction "A_A") (pintype "passive"))
      (node (ref "LED2") (pin "1") (pinfunction "GREEN_A_1") (pintype "bidirectional"))
      (node (ref "LED2") (pin "2") (pinfunction "RED_A_2") (pintype "bidirectional"))
      (node (ref "LED2") (pin "3") (pinfunction "BLUE_A_3") (pintype "bidirectional"))
      (node (ref "U$4") (pin "P5") (pinfunction "P$5_P5") (pintype "bidirectional"))
      (node (ref "VBUS") (pin "1") (pinfunction "1_1") (pintype "passive"))
    )
    (net (code "3") (name "5VJ") (class "Default")
      (node (ref "U$1") (pin "P$11") (pinfunction "P$11_P$11") (pintype "bidirectional"))
      (node (ref "VBUS") (pin "2") (pinfunction "2_2") (pintype "passive"))
    )
    (net (code "4") (name "CTS") (class "Default")
      (node (ref "FTDI") (pin "5") (pinfunction "5_5") (pintype "passive"))
    )
    (net (code "5") (name "GND") (class "Default")
      (node (ref "1N4742") (pin "A") (pinfunction "A_A") (pintype "passive"))
      (node (ref "3") (pin "2") (pinfunction "2_2") (pintype "passive"))
      (node (ref "3.3V1") (pin "P$2") (pinfunction "P$2_P$2") (pintype "bidirectional"))
      (node (ref "3.3VL") (pin "P$2") (pinfunction "P$2_P$2") (pintype "bidirectional"))
      (node (ref "3.3VR") (pin "P$2") (pinfunction "P$2_P$2") (pintype "bidirectional"))
      (node (ref "5") (pin "1") (pinfunction "1_1") (pintype "passive"))
      (node (ref "5V1") (pin "P$2") (pinfunction "P$2_P$2") (pintype "bidirectional"))
      (node (ref "7") (pin "1") (pinfunction "1_1") (pintype "passive"))
      (node (ref "8") (pin "1") (pinfunction "1_1") (pintype "passive"))
      (node (ref "9") (pin "1") (pinfunction "1_1") (pintype "passive"))
      (node (ref "C1") (pin "-") (pinfunction "-_-") (pintype "passive"))
      (node (ref "C10") (pin "2") (pinfunction "2_2") (pintype "passive"))
      (node (ref "C11") (pin "2") (pinfunction "2_2") (pintype "passive"))
      (node (ref "C12") (pin "-") (pinfunction "-_-") (pintype "passive"))
      (node (ref "C13") (pin "2") (pinfunction "2_2") (pintype "passive"))
      (node (ref "C14") (pin "2") (pinfunction "2_2") (pintype "passive"))
      (node (ref "C15") (pin "2") (pinfunction "2_2") (pintype "passive"))
      (node (ref "C16") (pin "2") (pinfunction "2_2") (pintype "passive"))
      (node (ref "C17") (pin "2") (pinfunction "2_2") (pintype "passive"))
      (node (ref "C18") (pin "2") (pinfunction "2_2") (pintype "passive"))
      (node (ref "C19") (pin "2") (pinfunction "2_2") (pintype "passive"))
      (node (ref "C2") (pin "2") (pinfunction "2_2") (pintype "passive"))
      (node (ref "C20") (pin "-") (pinfunction "-_-") (pintype "passive"))
      (node (ref "C21") (pin "-") (pinfunction "-_-") (pintype "passive"))
      (node (ref "C3") (pin "2") (pinfunction "2_2") (pintype "passive"))
      (node (ref "C30") (pin "2") (pinfunction "2_2") (pintype "passive"))
      (node (ref "C31") (pin "2") (pinfunction "2_2") (pintype "passive"))
      (node (ref "C32") (pin "-") (pinfunction "-_-") (pintype "passive"))
      (node (ref "C33") (pin "2") (pinfunction "2_2") (pintype "passive"))
      (node (ref "C34") (pin "2") (pinfunction "2_2") (pintype "passive"))
      (node (ref "C35") (pin "2") (pinfunction "2_2") (pintype "passive"))
      (node (ref "C36") (pin "2") (pinfunction "2_2") (pintype "passive"))
      (node (ref "C4") (pin "2") (pinfunction "2_2") (pintype "passive"))
      (node (ref "C8") (pin "2") (pinfunction "2_2") (pintype "passive"))
      (node (ref "C9") (pin "2") (pinfunction "2_2") (pintype "passive"))
      (node (ref "CON1") (pin "4") (pinfunction "4_4") (pintype "bidirectional"))
      (node (ref "CON2") (pin "4") (pinfunction "4_4") (pintype "bidirectional"))
      (node (ref "CON3") (pin "4") (pinfunction "4_4") (pintype "bidirectional"))
      (node (ref "CON4") (pin "4") (pinfunction "4_4") (pintype "bidirectional"))
      (node (ref "CON5") (pin "4") (pinfunction "4_4") (pintype "bidirectional"))
      (node (ref "CON6") (pin "4") (pinfunction "4_4") (pintype "bidirectional"))
      (node (ref "CON7") (pin "4") (pinfunction "4_4") (pintype "bidirectional"))
      (node (ref "FITPC") (pin "P$2") (pinfunction "P$2_P$2") (pintype "bidirectional"))
      (node (ref "FTDI") (pin "6") (pinfunction "6_6") (pintype "passive"))
      (node (ref "IC5") (pin "2") (pinfunction "GND_2") (pintype "passive"))
      (node (ref "IC5") (pin "4") (pinfunction "GND_4") (pintype "passive"))
      (node (ref "IMU") (pin "7") (pinfunction "7_7") (pintype "passive"))
      (node (ref "L1") (pin "C") (pinfunction "C_C") (pintype "passive"))
      (node (ref "L2") (pin "C") (pinfunction "C_C") (pintype "passive"))
      (node (ref "L3") (pin "C") (pinfunction "C_C") (pintype "passive"))
      (node (ref "LIPO_INPUT") (pin "1") (pinfunction "1_1") (pintype "passive"))
      (node (ref "Q2") (pin "2") (pinfunction "E_2") (pintype "passive"))
      (node (ref "RGBLED") (pin "1") (pinfunction "1_1") (pintype "passive"))
      (node (ref "T1") (pin "2") (pinfunction "E_2") (pintype "passive"))
      (node (ref "T2") (pin "2") (pinfunction "E_2") (pintype "passive"))
      (node (ref "T3") (pin "2") (pinfunction "E_2") (pintype "passive"))
      (node (ref "T4") (pin "2") (pinfunction "E_2") (pintype "passive"))
      (node (ref "T5") (pin "2") (pinfunction "E_2") (pintype "passive"))
      (node (ref "T6") (pin "2") (pinfunction "E_2") (pintype "passive"))
      (node (ref "T7") (pin "2") (pinfunction "E_2") (pintype "passive"))
      (node (ref "U$1") (pin "P$12") (pinfunction "P$12_P$12") (pintype "bidirectional"))
      (node (ref "U$1") (pin "P$31") (pinfunction "P$31_P$31") (pintype "bidirectional"))
      (node (ref "U$2") (pin "P$1") (pinfunction "1_P$1") (pintype "bidirectional"))
      (node (ref "U$4") (pin "P1") (pinfunction "P$1_P1") (pintype "bidirectional"))
      (node (ref "U1") (pin "4") (pinfunction "GND_4") (pintype "bidirectional"))
      (node (ref "U2") (pin "4") (pinfunction "GND_4") (pintype "bidirectional"))
      (node (ref "U3") (pin "4") (pinfunction "GND_4") (pintype "bidirectional"))
      (node (ref "U4") (pin "4") (pinfunction "GND_4") (pintype "bidirectional"))
      (node (ref "U5") (pin "4") (pinfunction "GND_4") (pintype "bidirectional"))
      (node (ref "U6") (pin "4") (pinfunction "GND_4") (pintype "bidirectional"))
      (node (ref "U7") (pin "4") (pinfunction "GND_4") (pintype "bidirectional"))
      (node (ref "V8ZA2P-1") (pin "P$1") (pinfunction "P$1_P$1") (pintype "bidirectional"))
      (node (ref "V8ZA2P-2") (pin "P$1") (pinfunction "P$1_P$1") (pintype "bidirectional"))
      (node (ref "V8ZA2P-3") (pin "P$2") (pinfunction "P$2_P$2") (pintype "bidirectional"))
      (node (ref "V8ZA2P-4") (pin "P$2") (pinfunction "P$2_P$2") (pintype "bidirectional"))
    )
    (net (code "6") (name "HX_RX") (class "Default")
      (node (ref "14") (pin "1") (pinfunction "1_1") (pintype "passive"))
      (node (ref "CON1") (pin "1") (pinfunction "1_1") (pintype "bidirectional"))
      (node (ref "CON2") (pin "1") (pinfunction "1_1") (pintype "bidirectional"))
      (node (ref "CON3") (pin "1") (pinfunction "1_1") (pintype "bidirectional"))
      (node (ref "CON4") (pin "1") (pinfunction "1_1") (pintype "bidirectional"))
      (node (ref "CON5") (pin "1") (pinfunction "1_1") (pintype "bidirectional"))
      (node (ref "CON6") (pin "1") (pinfunction "1_1") (pintype "bidirectional"))
      (node (ref "CON7") (pin "1") (pinfunction "1_1") (pintype "bidirectional"))
      (node (ref "FTDI") (pin "3") (pinfunction "3_3") (pintype "passive"))
      (node (ref "RX") (pin "2") (pinfunction "2_2") (pintype "passive"))
      (node (ref "U1") (pin "5") (pinfunction "IO2_5") (pintype "bidirectional"))
      (node (ref "U2") (pin "5") (pinfunction "IO2_5") (pintype "bidirectional"))
      (node (ref "U3") (pin "5") (pinfunction "IO2_5") (pintype "bidirectional"))
      (node (ref "U4") (pin "5") (pinfunction "IO2_5") (pintype "bidirectional"))
      (node (ref "U5") (pin "5") (pinfunction "IO2_5") (pintype "bidirectional"))
      (node (ref "U6") (pin "5") (pinfunction "IO2_5") (pintype "bidirectional"))
      (node (ref "U7") (pin "5") (pinfunction "IO2_5") (pintype "bidirectional"))
      (node (ref "V8ZA2P-1") (pin "P$2") (pinfunction "P$2_P$2") (pintype "bidirectional"))
      (node (ref "V8ZA2P-3") (pin "P$1") (pinfunction "P$1_P$1") (pintype "bidirectional"))
    )
    (net (code "7") (name "HX_TX") (class "Default")
      (node (ref "15") (pin "1") (pinfunction "1_1") (pintype "passive"))
      (node (ref "CON1") (pin "2") (pinfunction "2_2") (pintype "bidirectional"))
      (node (ref "CON2") (pin "2") (pinfunction "2_2") (pintype "bidirectional"))
      (node (ref "CON3") (pin "2") (pinfunction "2_2") (pintype "bidirectional"))
      (node (ref "CON4") (pin "2") (pinfunction "2_2") (pintype "bidirectional"))
      (node (ref "CON5") (pin "2") (pinfunction "2_2") (pintype "bidirectional"))
      (node (ref "CON6") (pin "2") (pinfunction "2_2") (pintype "bidirectional"))
      (node (ref "CON7") (pin "2") (pinfunction "2_2") (pintype "bidirectional"))
      (node (ref "FTDI") (pin "2") (pinfunction "2_2") (pintype "passive"))
      (node (ref "TX") (pin "2") (pinfunction "2_2") (pintype "passive"))
      (node (ref "U1") (pin "3") (pinfunction "IO1_3") (pintype "input"))
      (node (ref "U2") (pin "3") (pinfunction "IO1_3") (pintype "input"))
      (node (ref "U3") (pin "3") (pinfunction "IO1_3") (pintype "input"))
      (node (ref "U4") (pin "3") (pinfunction "IO1_3") (pintype "input"))
      (node (ref "U5") (pin "3") (pinfunction "IO1_3") (pintype "input"))
      (node (ref "U6") (pin "3") (pinfunction "IO1_3") (pintype "input"))
      (node (ref "U7") (pin "3") (pinfunction "IO1_3") (pintype "input"))
      (node (ref "V8ZA2P-2") (pin "P$2") (pinfunction "P$2_P$2") (pintype "bidirectional"))
      (node (ref "V8ZA2P-4") (pin "P$1") (pinfunction "P$1_P$1") (pintype "bidirectional"))
    )
    (net (code "8") (name "MOSFET_CTRL") (class "Default")
      (node (ref "Q7") (pin "3") (pinfunction "S_3") (pintype "passive"))
      (node (ref "TX1") (pin "1") (pinfunction "1_1") (pintype "passive"))
    )
    (net (code "9") (name "Net-(1-Pad1)") (class "Default")
      (node (ref "1") (pin "1") (pinfunction "1_1") (pintype "passive"))
      (node (ref "L1") (pin "A") (pinfunction "A_A") (pintype "passive"))
    )
    (net (code "10") (name "Net-(14-Pad2)") (class "Default")
      (node (ref "14") (pin "2") (pinfunction "2_2") (pintype "passive"))
      (node (ref "L2") (pin "A") (pinfunction "A_A") (pintype "passive"))
    )
    (net (code "11") (name "Net-(15-Pad2)") (class "Default")
      (node (ref "15") (pin "2") (pinfunction "2_2") (pintype "passive"))
      (node (ref "L3") (pin "A") (pinfunction "A_A") (pintype "passive"))
    )
    (net (code "12") (name "Net-(16-Pad2)") (class "Default")
      (node (ref "16") (pin "2") (pinfunction "2_2") (pintype "passive"))
      (node (ref "L4") (pin "C") (pinfunction "C_C") (pintype "passive"))
    )
    (net (code "13") (name "Net-(18-Pad2)") (class "Default")
      (node (ref "18") (pin "2") (pinfunction "2_2") (pintype "passive"))
      (node (ref "L5") (pin "C") (pinfunction "C_C") (pintype "passive"))
    )
    (net (code "14") (name "Net-(20-Pad2)") (class "Default")
      (node (ref "20") (pin "2") (pinfunction "2_2") (pintype "passive"))
      (node (ref "L6") (pin "C") (pinfunction "C_C") (pintype "passive"))
    )
    (net (code "15") (name "Net-(20A-Pad1)") (class "Default")
      (node (ref "20A") (pin "1") (pinfunction "1_1") (pintype "passive"))
      (node (ref "LIPO_INPUT") (pin "2") (pinfunction "2_2") (pintype "passive"))
    )
    (net (code "16") (name "Net-(20A-Pad2)") (class "Default")
      (node (ref "20A") (pin "2") (pinfunction "2_2") (pintype "passive"))
      (node (ref "PWR_SW") (pin "1") (pinfunction "1_1") (pintype "passive"))
    )
    (net (code "17") (name "Net-(22-Pad2)") (class "Default")
      (node (ref "22") (pin "2") (pinfunction "2_2") (pintype "passive"))
      (node (ref "L7") (pin "C") (pinfunction "C_C") (pintype "passive"))
    )
    (net (code "18") (name "Net-(BUZZER-2)") (class "Default")
      (node (ref "BUZZER") (pin "-") (pinfunction "2_-") (pintype "passive"))
      (node (ref "Q2") (pin "3") (pinfunction "C_3") (pintype "passive"))
    )
    (net (code "19") (name "Net-(C13-Pad1)") (class "Default")
      (node (ref "C13") (pin "1") (pinfunction "1_1") (pintype "passive"))
      (node (ref "C14") (pin "1") (pinfunction "1_1") (pintype "passive"))
      (node (ref "C15") (pin "1") (pinfunction "1_1") (pintype "passive"))
      (node (ref "C16") (pin "1") (pinfunction "1_1") (pintype "passive"))
      (node (ref "C17") (pin "1") (pinfunction "1_1") (pintype "passive"))
      (node (ref "C18") (pin "1") (pinfunction "1_1") (pintype "passive"))
      (node (ref "C19") (pin "1") (pinfunction "1_1") (pintype "passive"))
      (node (ref "C20") (pin "+") (pinfunction "+_+") (pintype "passive"))
      (node (ref "C21") (pin "+") (pinfunction "+_+") (pintype "passive"))
      (node (ref "CON1") (pin "3") (pinfunction "3_3") (pintype "bidirectional"))
      (node (ref "CON2") (pin "3") (pinfunction "3_3") (pintype "bidirectional"))
      (node (ref "CON3") (pin "3") (pinfunction "3_3") (pintype "bidirectional"))
      (node (ref "CON4") (pin "3") (pinfunction "3_3") (pintype "bidirectional"))
      (node (ref "CON5") (pin "3") (pinfunction "3_3") (pintype "bidirectional"))
      (node (ref "CON6") (pin "3") (pinfunction "3_3") (pintype "bidirectional"))
      (node (ref "CON7") (pin "3") (pinfunction "3_3") (pintype "bidirectional"))
      (node (ref "TX1") (pin "2") (pinfunction "2_2") (pintype "passive"))
    )
    (net (code "20") (name "Net-(FTDI-Pad1)") (class "Default")
      (node (ref "FTDI") (pin "1") (pinfunction "1_1") (pintype "passive"))
      (node (ref "RST") (pin "2") (pinfunction "2_2") (pintype "passive"))
    )
    (net (code "21") (name "Net-(IC5-VIN)") (class "Default")
      (node (ref "C9") (pin "1") (pinfunction "1_1") (pintype "passive"))
      (node (ref "D2") (pin "C") (pinfunction "C_C") (pintype "passive"))
      (node (ref "IC5") (pin "1") (pinfunction "VIN_1") (pintype "input"))
    )
    (net (code "22") (name "Net-(LED2-BLUE_C)") (class "Default")
      (node (ref "30") (pin "1") (pinfunction "1_1") (pintype "passive"))
      (node (ref "LED2") (pin "4") (pinfunction "BLUE_C_4") (pintype "bidirectional"))
      (node (ref "RGBLED") (pin "2") (pinfunction "1_2") (pintype "passive"))
    )
    (net (code "23") (name "Net-(LED2-GREEN_C)") (class "Default")
      (node (ref "34") (pin "2") (pinfunction "2_2") (pintype "passive"))
      (node (ref "LED2") (pin "6") (pinfunction "GREEN_C_6") (pintype "bidirectional"))
      (node (ref "RGBLED") (pin "4") (pinfunction "1_4") (pintype "passive"))
    )
    (net (code "24") (name "Net-(LED2-RED_C)") (class "Default")
      (node (ref "32") (pin "2") (pinfunction "2_2") (pintype "passive"))
      (node (ref "LED2") (pin "5") (pinfunction "RED_C_5") (pintype "bidirectional"))
      (node (ref "RGBLED") (pin "3") (pinfunction "1_3") (pintype "passive"))
    )
    (net (code "25") (name "Net-(Q2-B)") (class "Default")
      (node (ref "24") (pin "1") (pinfunction "1_1") (pintype "passive"))
      (node (ref "Q2") (pin "1") (pinfunction "B_1") (pintype "passive"))
    )
    (net (code "26") (name "Net-(T1-B)") (class "Default")
      (node (ref "33") (pin "2") (pinfunction "2_2") (pintype "passive"))
      (node (ref "T1") (pin "1") (pinfunction "B_1") (pintype "passive"))
    )
    (net (code "27") (name "Net-(T1-C)") (class "Default")
      (node (ref "34") (pin "1") (pinfunction "1_1") (pintype "passive"))
      (node (ref "T1") (pin "3") (pinfunction "C_3") (pintype "passive"))
    )
    (net (code "28") (name "Net-(T2-B)") (class "Default")
      (node (ref "31") (pin "2") (pinfunction "2_2") (pintype "passive"))
      (node (ref "T2") (pin "1") (pinfunction "B_1") (pintype "passive"))
    )
    (net (code "29") (name "Net-(T2-C)") (class "Default")
      (node (ref "32") (pin "1") (pinfunction "1_1") (pintype "passive"))
      (node (ref "T2") (pin "3") (pinfunction "C_3") (pintype "passive"))
    )
    (net (code "30") (name "Net-(T3-B)") (class "Default")
      (node (ref "29") (pin "2") (pinfunction "2_2") (pintype "passive"))
      (node (ref "T3") (pin "1") (pinfunction "B_1") (pintype "passive"))
    )
    (net (code "31") (name "Net-(T3-C)") (class "Default")
      (node (ref "30") (pin "2") (pinfunction "2_2") (pintype "passive"))
      (node (ref "T3") (pin "3") (pinfunction "C_3") (pintype "passive"))
    )
    (net (code "32") (name "Net-(T4-B)") (class "Default")
      (node (ref "19") (pin "2") (pinfunction "2_2") (pintype "passive"))
      (node (ref "T4") (pin "1") (pinfunction "B_1") (pintype "passive"))
    )
    (net (code "33") (name "Net-(T4-C)") (class "Default")
      (node (ref "18") (pin "1") (pinfunction "1_1") (pintype "passive"))
      (node (ref "T4") (pin "3") (pinfunction "C_3") (pintype "passive"))
    )
    (net (code "34") (name "Net-(T5-B)") (class "Default")
      (node (ref "17") (pin "2") (pinfunction "2_2") (pintype "passive"))
      (node (ref "T5") (pin "1") (pinfunction "B_1") (pintype "passive"))
    )
    (net (code "35") (name "Net-(T5-C)") (class "Default")
      (node (ref "16") (pin "1") (pinfunction "1_1") (pintype "passive"))
      (node (ref "T5") (pin "3") (pinfunction "C_3") (pintype "passive"))
    )
    (net (code "36") (name "Net-(T6-B)") (class "Default")
      (node (ref "23") (pin "2") (pinfunction "2_2") (pintype "passive"))
      (node (ref "T6") (pin "1") (pinfunction "B_1") (pintype "passive"))
    )
    (net (code "37") (name "Net-(T6-C)") (class "Default")
      (node (ref "22") (pin "1") (pinfunction "1_1") (pintype "passive"))
      (node (ref "T6") (pin "3") (pinfunction "C_3") (pintype "passive"))
    )
    (net (code "38") (name "Net-(T7-B)") (class "Default")
      (node (ref "21") (pin "2") (pinfunction "2_2") (pintype "passive"))
      (node (ref "T7") (pin "1") (pinfunction "B_1") (pintype "passive"))
    )
    (net (code "39") (name "Net-(T7-C)") (class "Default")
      (node (ref "20") (pin "1") (pinfunction "1_1") (pintype "passive"))
      (node (ref "T7") (pin "3") (pinfunction "C_3") (pintype "passive"))
    )
    (net (code "40") (name "Net-(U$2-2)") (class "Default")
      (node (ref "2") (pin "1") (pinfunction "1_1") (pintype "passive"))
      (node (ref "U$2") (pin "P$2") (pinfunction "2_P$2") (pintype "bidirectional"))
    )
    (net (code "41") (name "Net-(U$2-3)") (class "Default")
      (node (ref "4") (pin "2") (pinfunction "2_2") (pintype "passive"))
      (node (ref "U$2") (pin "P$3") (pinfunction "3_P$3") (pintype "bidirectional"))
    )
    (net (code "42") (name "Net-(U$2-4)") (class "Default")
      (node (ref "6") (pin "2") (pinfunction "2_2") (pintype "passive"))
      (node (ref "U$2") (pin "P$4") (pinfunction "4_P$4") (pintype "bidirectional"))
    )
    (net (code "43") (name "Net-(U$4-P$4)") (class "Default")
      (node (ref "9") (pin "2") (pinfunction "2_2") (pintype "passive"))
      (node (ref "U$4") (pin "P4") (pinfunction "P$4_P4") (pintype "bidirectional"))
    )
    (net (code "44") (name "P2") (class "Default")
      (node (ref "FL") (pin "4") (pinfunction "1_4") (pintype "passive"))
      (node (ref "U$1") (pin "P$2") (pinfunction "P$2_P$2") (pintype "bidirectional"))
    )
    (net (code "45") (name "P3") (class "Default")
      (node (ref "P3") (pin "1") (pinfunction "1_1") (pintype "passive"))
      (node (ref "U$1") (pin "P$3") (pinfunction "P$3_P$3") (pintype "bidirectional"))
    )
    (net (code "46") (name "P4") (class "Default")
      (node (ref "P4") (pin "1") (pinfunction "1_1") (pintype "passive"))
      (node (ref "U$1") (pin "P$4") (pinfunction "P$4_P$4") (pintype "bidirectional"))
    )
    (net (code "47") (name "P5") (class "Default")
      (node (ref "6") (pin "1") (pinfunction "1_1") (pintype "passive"))
      (node (ref "7") (pin "2") (pinfunction "2_2") (pintype "passive"))
      (node (ref "C4") (pin "1") (pinfunction "1_1") (pintype "passive"))
      (node (ref "U$1") (pin "P$5") (pinfunction "P$5_P$5") (pintype "bidirectional"))
    )
    (net (code "48") (name "P6") (class "Default")
      (node (ref "4") (pin "1") (pinfunction "1_1") (pintype "passive"))
      (node (ref "5") (pin "2") (pinfunction "2_2") (pintype "passive"))
      (node (ref "C3") (pin "1") (pinfunction "1_1") (pintype "passive"))
      (node (ref "U$1") (pin "P$6") (pinfunction "P$6_P$6") (pintype "bidirectional"))
    )
    (net (code "49") (name "P7") (class "Default")
      (node (ref "2") (pin "2") (pinfunction "2_2") (pintype "passive"))
      (node (ref "3") (pin "1") (pinfunction "1_1") (pintype "passive"))
      (node (ref "C2") (pin "1") (pinfunction "1_1") (pintype "passive"))
      (node (ref "U$1") (pin "P$7") (pinfunction "P$7_P$7") (pintype "bidirectional"))
    )
    (net (code "50") (name "P8") (class "Default")
      (node (ref "17") (pin "1") (pinfunction "1_1") (pintype "passive"))
      (node (ref "LED") (pin "4") (pinfunction "1_4") (pintype "passive"))
      (node (ref "U$1") (pin "P$8") (pinfunction "P$8_P$8") (pintype "bidirectional"))
    )
    (net (code "51") (name "P9") (class "Default")
      (node (ref "19") (pin "1") (pinfunction "1_1") (pintype "passive"))
      (node (ref "LED") (pin "3") (pinfunction "1_3") (pintype "passive"))
      (node (ref "U$1") (pin "P$9") (pinfunction "P$9_P$9") (pintype "bidirectional"))
    )
    (net (code "52") (name "P10") (class "Default")
      (node (ref "21") (pin "1") (pinfunction "1_1") (pintype "passive"))
      (node (ref "LED") (pin "2") (pinfunction "1_2") (pintype "passive"))
      (node (ref "U$1") (pin "P$10") (pinfunction "P$10_P$10") (pintype "bidirectional"))
    )
    (net (code "53") (name "P13") (class "Default")
      (node (ref "FL") (pin "3") (pinfunction "1_3") (pintype "passive"))
      (node (ref "U$1") (pin "P$13") (pinfunction "P$13_P$13") (pintype "bidirectional"))
    )
    (net (code "54") (name "P14") (class "Default")
      (node (ref "FL") (pin "2") (pinfunction "1_2") (pintype "passive"))
      (node (ref "U$1") (pin "P$14") (pinfunction "P$14_P$14") (pintype "bidirectional"))
    )
    (net (code "55") (name "P15") (class "Default")
      (node (ref "FL") (pin "1") (pinfunction "1_1") (pintype "passive"))
      (node (ref "U$1") (pin "P$15") (pinfunction "P$15_P$15") (pintype "bidirectional"))
    )
    (net (code "56") (name "P16") (class "Default")
      (node (ref "FR") (pin "4") (pinfunction "1_4") (pintype "passive"))
      (node (ref "U$1") (pin "P$16") (pinfunction "P$16_P$16") (pintype "bidirectional"))
    )
    (net (code "57") (name "P17") (class "Default")
      (node (ref "FR") (pin "3") (pinfunction "1_3") (pintype "passive"))
      (node (ref "U$1") (pin "P$17") (pinfunction "P$17_P$17") (pintype "bidirectional"))
    )
    (net (code "58") (name "P18") (class "Default")
      (node (ref "FR") (pin "2") (pinfunction "1_2") (pintype "passive"))
      (node (ref "U$1") (pin "P$18") (pinfunction "P$18_P$18") (pintype "bidirectional"))
    )
    (net (code "59") (name "P19") (class "Default")
      (node (ref "FR") (pin "1") (pinfunction "1_1") (pintype "passive"))
      (node (ref "U$1") (pin "P$19") (pinfunction "P$19_P$19") (pintype "bidirectional"))
    )
    (net (code "60") (name "P20") (class "Default")
      (node (ref "23") (pin "1") (pinfunction "1_1") (pintype "passive"))
      (node (ref "LED") (pin "1") (pinfunction "1_1") (pintype "passive"))
      (node (ref "U$1") (pin "P$20") (pinfunction "P$20_P$20") (pintype "bidirectional"))
    )
    (net (code "61") (name "P21") (class "Default")
      (node (ref "P21") (pin "1") (pinfunction "1_1") (pintype "passive"))
      (node (ref "U$1") (pin "P$21") (pinfunction "P$21_P$21") (pintype "bidirectional"))
    )
    (net (code "62") (name "P22") (class "Default")
      (node (ref "P22") (pin "1") (pinfunction "1_1") (pintype "passive"))
      (node (ref "U$1") (pin "P$22") (pinfunction "P$22_P$22") (pintype "bidirectional"))
    )
    (net (code "63") (name "P23") (class "Default")
      (node (ref "24") (pin "2") (pinfunction "2_2") (pintype "passive"))
      (node (ref "P23") (pin "1") (pinfunction "1_1") (pintype "passive"))
      (node (ref "U$1") (pin "P$23") (pinfunction "P$23_P$23") (pintype "bidirectional"))
    )
    (net (code "64") (name "P24") (class "Default")
      (node (ref "12") (pin "1") (pinfunction "1_1") (pintype "passive"))
      (node (ref "Q1") (pin "2") (pinfunction "S_2") (pintype "passive"))
      (node (ref "U$1") (pin "P$24") (pinfunction "P$24_P$24") (pintype "bidirectional"))
    )
    (net (code "65") (name "P25") (class "Default")
      (node (ref "10") (pin "1") (pinfunction "1_1") (pintype "passive"))
      (node (ref "Q5") (pin "3") (pinfunction "D_3") (pintype "passive"))
      (node (ref "U$1") (pin "P$25") (pinfunction "P$25_P$25") (pintype "bidirectional"))
    )
    (net (code "66") (name "P28") (class "Default")
      (node (ref "27") (pin "1") (pinfunction "1_1") (pintype "passive"))
      (node (ref "C35") (pin "1") (pinfunction "1_1") (pintype "passive"))
      (node (ref "SW") (pin "2") (pinfunction "1_2") (pintype "passive"))
      (node (ref "U$1") (pin "P$28") (pinfunction "P$28_P$28") (pintype "bidirectional"))
    )
    (net (code "67") (name "P29") (class "Default")
      (node (ref "26") (pin "1") (pinfunction "1_1") (pintype "passive"))
      (node (ref "C34") (pin "1") (pinfunction "1_1") (pintype "passive"))
      (node (ref "SW") (pin "3") (pinfunction "1_3") (pintype "passive"))
      (node (ref "U$1") (pin "P$29") (pinfunction "P$29_P$29") (pintype "bidirectional"))
    )
    (net (code "68") (name "P30") (class "Default")
      (node (ref "25") (pin "1") (pinfunction "1_1") (pintype "passive"))
      (node (ref "C33") (pin "1") (pinfunction "1_1") (pintype "passive"))
      (node (ref "SW") (pin "4") (pinfunction "1_4") (pintype "passive"))
      (node (ref "U$1") (pin "P$30") (pinfunction "P$30_P$30") (pintype "bidirectional"))
    )
    (net (code "69") (name "P32") (class "Default")
      (node (ref "IMU") (pin "1") (pinfunction "1_1") (pintype "passive"))
      (node (ref "U$1") (pin "P$32") (pinfunction "P$32_P$32") (pintype "bidirectional"))
    )
    (net (code "70") (name "P33") (class "Default")
      (node (ref "8") (pin "2") (pinfunction "2_2") (pintype "passive"))
      (node (ref "Q7") (pin "1") (pinfunction "G_1") (pintype "passive"))
      (node (ref "U$1") (pin "P$33") (pinfunction "P$33_P$33") (pintype "bidirectional"))
    )
    (net (code "71") (name "P34") (class "Default")
      (node (ref "28") (pin "1") (pinfunction "1_1") (pintype "passive"))
      (node (ref "C36") (pin "1") (pinfunction "1_1") (pintype "passive"))
      (node (ref "SW") (pin "1") (pinfunction "1_1") (pintype "passive"))
      (node (ref "U$1") (pin "P$34") (pinfunction "P$34_P$34") (pintype "bidirectional"))
    )
    (net (code "72") (name "P35") (class "Default")
      (node (ref "RST") (pin "1") (pinfunction "1_1") (pintype "passive"))
      (node (ref "U$1") (pin "P$35") (pinfunction "P$35_P$35") (pintype "bidirectional"))
    )
    (net (code "73") (name "P36") (class "Default")
      (node (ref "IMU") (pin "5") (pinfunction "5_5") (pintype "passive"))
      (node (ref "U$1") (pin "P$36") (pinfunction "P$36_P$36") (pintype "bidirectional"))
    )
    (net (code "74") (name "P37") (class "Default")
      (node (ref "IMU") (pin "6") (pinfunction "6_6") (pintype "passive"))
      (node (ref "U$1") (pin "P$37") (pinfunction "P$37_P$37") (pintype "bidirectional"))
    )
    (net (code "75") (name "P38") (class "Default")
      (node (ref "29") (pin "1") (pinfunction "1_1") (pintype "passive"))
      (node (ref "U$1") (pin "P$38") (pinfunction "P$38_P$38") (pintype "bidirectional"))
    )
    (net (code "76") (name "P39") (class "Default")
      (node (ref "31") (pin "1") (pinfunction "1_1") (pintype "passive"))
      (node (ref "U$1") (pin "P$39") (pinfunction "P$39_P$39") (pintype "bidirectional"))
    )
    (net (code "77") (name "P40") (class "Default")
      (node (ref "33") (pin "1") (pinfunction "1_1") (pintype "passive"))
      (node (ref "U$1") (pin "P$40") (pinfunction "P$40_P$40") (pintype "bidirectional"))
    )
    (net (code "78") (name "RX3") (class "Default")
      (node (ref "P26") (pin "1") (pinfunction "1_1") (pintype "passive"))
      (node (ref "U$1") (pin "P$26") (pinfunction "P$26_P$26") (pintype "bidirectional"))
    )
    (net (code "79") (name "TIVA_RX") (class "Default")
      (node (ref "13") (pin "1") (pinfunction "1_1") (pintype "passive"))
      (node (ref "Q1") (pin "3") (pinfunction "D_3") (pintype "passive"))
      (node (ref "TX") (pin "1") (pinfunction "1_1") (pintype "passive"))
    )
    (net (code "80") (name "TIVA_TX") (class "Default")
      (node (ref "11") (pin "1") (pinfunction "1_1") (pintype "passive"))
      (node (ref "Q5") (pin "2") (pinfunction "S_2") (pintype "passive"))
      (node (ref "RX") (pin "1") (pinfunction "1_1") (pintype "passive"))
    )
    (net (code "81") (name "TX3") (class "Default")
      (node (ref "P27") (pin "1") (pinfunction "1_1") (pintype "passive"))
      (node (ref "U$1") (pin "P$27") (pinfunction "P$27_P$27") (pintype "bidirectional"))
    )
    (net (code "82") (name "VCC") (class "Default")
      (node (ref "1") (pin "2") (pinfunction "2_2") (pintype "passive"))
      (node (ref "1N4742") (pin "C") (pinfunction "C_C") (pintype "passive"))
      (node (ref "C1") (pin "+") (pinfunction "+_+") (pintype "passive"))
      (node (ref "C11") (pin "1") (pinfunction "1_1") (pintype "passive"))
      (node (ref "C8") (pin "1") (pinfunction "1_1") (pintype "passive"))
      (node (ref "FITPC") (pin "P$1") (pinfunction "P$1_P$1") (pintype "bidirectional"))
      (node (ref "PWR_SW") (pin "2") (pinfunction "2_2") (pintype "passive"))
      (node (ref "Q7") (pin "2") (pinfunction "D_2") (pintype "passive"))
      (node (ref "U$4") (pin "P2") (pinfunction "P$2_P2") (pintype "bidirectional"))
    )
    (net (code "83") (name "unconnected-(IMU-Pad2)") (class "Default")
      (node (ref "IMU") (pin "2") (pinfunction "2_2") (pintype "passive"))
    )
    (net (code "84") (name "unconnected-(IMU-Pad3)") (class "Default")
      (node (ref "IMU") (pin "3") (pinfunction "3_3") (pintype "passive"))
    )
    (net (code "85") (name "unconnected-(IMU-Pad4)") (class "Default")
      (node (ref "IMU") (pin "4") (pinfunction "4_4") (pintype "passive"))
    )
    (net (code "86") (name "unconnected-(U$1-PadP$1)") (class "Default")
      (node (ref "U$1") (pin "P$1") (pinfunction "P$1_P$1") (pintype "bidirectional"))
    )
    (net (code "87") (name "unconnected-(U$4-P$3-PadP3)") (class "Default")
      (node (ref "U$4") (pin "P3") (pinfunction "P$3_P3") (pintype "bidirectional"))
    )
    (net (code "88") (name "unconnected-(U1-NC-1-Pad1)") (class "Default")
      (node (ref "U1") (pin "1") (pinfunction "NC-1_1") (pintype "no_connect"))
    )
    (net (code "89") (name "unconnected-(U1-NC-2-Pad2)") (class "Default")
      (node (ref "U1") (pin "2") (pinfunction "NC-2_2") (pintype "no_connect"))
    )
    (net (code "90") (name "unconnected-(U2-NC-1-Pad1)") (class "Default")
      (node (ref "U2") (pin "1") (pinfunction "NC-1_1") (pintype "no_connect"))
    )
    (net (code "91") (name "unconnected-(U2-NC-2-Pad2)") (class "Default")
      (node (ref "U2") (pin "2") (pinfunction "NC-2_2") (pintype "no_connect"))
    )
    (net (code "92") (name "unconnected-(U3-NC-1-Pad1)") (class "Default")
      (node (ref "U3") (pin "1") (pinfunction "NC-1_1") (pintype "no_connect"))
    )
    (net (code "93") (name "unconnected-(U3-NC-2-Pad2)") (class "Default")
      (node (ref "U3") (pin "2") (pinfunction "NC-2_2") (pintype "no_connect"))
    )
    (net (code "94") (name "unconnected-(U4-NC-1-Pad1)") (class "Default")
      (node (ref "U4") (pin "1") (pinfunction "NC-1_1") (pintype "no_connect"))
    )
    (net (code "95") (name "unconnected-(U4-NC-2-Pad2)") (class "Default")
      (node (ref "U4") (pin "2") (pinfunction "NC-2_2") (pintype "no_connect"))
    )
    (net (code "96") (name "unconnected-(U5-NC-1-Pad1)") (class "Default")
      (node (ref "U5") (pin "1") (pinfunction "NC-1_1") (pintype "no_connect"))
    )
    (net (code "97") (name "unconnected-(U5-NC-2-Pad2)") (class "Default")
      (node (ref "U5") (pin "2") (pinfunction "NC-2_2") (pintype "no_connect"))
    )
    (net (code "98") (name "unconnected-(U6-NC-1-Pad1)") (class "Default")
      (node (ref "U6") (pin "1") (pinfunction "NC-1_1") (pintype "no_connect"))
    )
    (net (code "99") (name "unconnected-(U6-NC-2-Pad2)") (class "Default")
      (node (ref "U6") (pin "2") (pinfunction "NC-2_2") (pintype "no_connect"))
    )
    (net (code "100") (name "unconnected-(U7-NC-1-Pad1)") (class "Default")
      (node (ref "U7") (pin "1") (pinfunction "NC-1_1") (pintype "no_connect"))
    )
    (net (code "101") (name "unconnected-(U7-NC-2-Pad2)") (class "Default")
      (node (ref "U7") (pin "2") (pinfunction "NC-2_2") (pintype "no_connect"))
    )
  )
)
